# hamp1.net
KiCad netlist of a schematic drawn in EAGLE
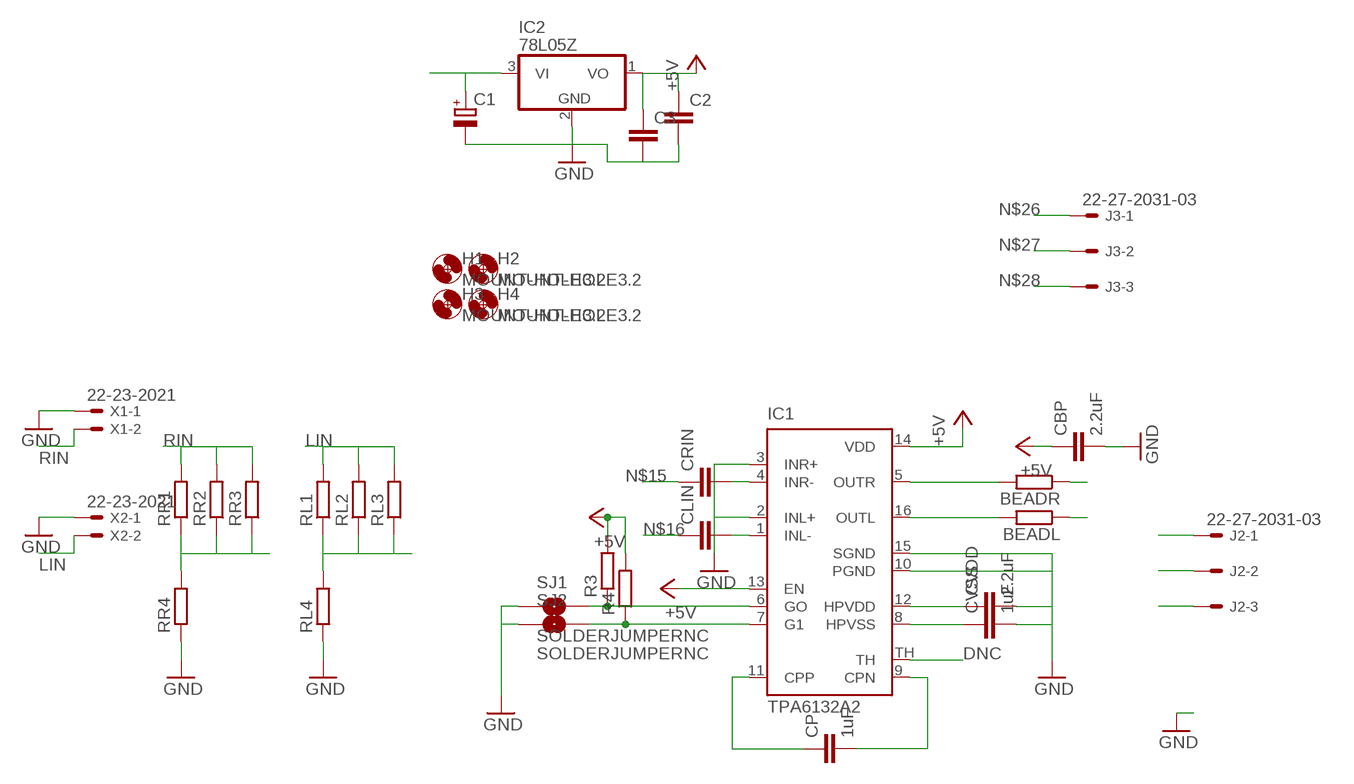
[diagram p0: schematic, sheet 1]

(export (version "E")
  (design (tool "Eeschema 10.0.6"))
  (components
    (comp (ref "BEADL")
      (value "R-EU_R0805")
      (footprint "eagle-import:R0805")
      (libsource (lib "eagle-import") (part "R-EU_R0805"))
    )
    (comp (ref "BEADR")
      (value "R-EU_R0805")
      (footprint "eagle-import:R0805")
      (libsource (lib "eagle-import") (part "R-EU_R0805"))
    )
    (comp (ref "C1")
      (value "CPOL-EUF")
      (footprint "eagle-import:PANASONIC_F")
      (libsource (lib "eagle-import") (part "CPOL-EUF"))
    )
    (comp (ref "C2")
      (value "C-EUC1210")
      (footprint "eagle-import:C1210")
      (libsource (lib "eagle-import") (part "resistor_C-EUC1210"))
    )
    (comp (ref "C3")
      (value "C-EUC0805")
      (footprint "eagle-import:C0805")
      (libsource (lib "eagle-import") (part "resistor_C-EUC0805"))
    )
    (comp (ref "CBP")
      (value "2.2uF")
      (footprint "eagle-import:C0805")
      (libsource (lib "eagle-import") (part "resistor_C-EUC0805"))
    )
    (comp (ref "CLIN")
      (value "C-EU050-055X075")
      (footprint "eagle-import:C050-055X075")
      (libsource (lib "eagle-import") (part "C-EU050-055X075"))
    )
    (comp (ref "CP")
      (value "1uF")
      (footprint "eagle-import:C0805")
      (libsource (lib "eagle-import") (part "resistor_C-EUC0805"))
    )
    (comp (ref "CRIN")
      (value "C-EU050-055X075")
      (footprint "eagle-import:C050-055X075")
      (libsource (lib "eagle-import") (part "C-EU050-055X075"))
    )
    (comp (ref "CVDD")
      (value "2.2uF")
      (footprint "eagle-import:C0805")
      (libsource (lib "eagle-import") (part "resistor_C-EUC0805"))
    )
    (comp (ref "CVSS")
      (value "1uF")
      (footprint "eagle-import:C0805")
      (libsource (lib "eagle-import") (part "resistor_C-EUC0805"))
    )
    (comp (ref "H1")
      (value "MOUNT-HOLE3.2")
      (footprint "eagle-import:3,2")
      (libsource (lib "eagle-import") (part "MOUNT-HOLE3.2"))
    )
    (comp (ref "H2")
      (value "MOUNT-HOLE3.2")
      (footprint "eagle-import:3,2")
      (libsource (lib "eagle-import") (part "MOUNT-HOLE3.2"))
    )
    (comp (ref "H3")
      (value "MOUNT-HOLE3.2")
      (footprint "eagle-import:3,2")
      (libsource (lib "eagle-import") (part "MOUNT-HOLE3.2"))
    )
    (comp (ref "H4")
      (value "MOUNT-HOLE3.2")
      (footprint "eagle-import:3,2")
      (libsource (lib "eagle-import") (part "MOUNT-HOLE3.2"))
    )
    (comp (ref "IC1")
      (value "TPA6132A2")
      (footprint "eagle-import:QFN16")
      (fields (field (name "MPN") "TPA6132A2RTET"))
      (libsource (lib "eagle-import") (part "TPA6132A2"))
    )
    (comp (ref "IC2")
      (value "78L05Z")
      (footprint "eagle-import:TO92")
      (libsource (lib "eagle-import") (part "78ZL05"))
    )
    (comp (ref "J2")
      (value "22-27-2031-03")
      (footprint "eagle-import:6410-03")
      (fields (field (name "OC_FARNELL") "unknown") (field (name "OC_NEWARK") "unknown"))
      (libsource (lib "eagle-import") (part "22-?-0327-2031"))
    )
    (comp (ref "J3")
      (value "22-27-2031-03")
      (footprint "eagle-import:6410-03")
      (fields (field (name "OC_FARNELL") "unknown") (field (name "OC_NEWARK") "unknown"))
      (libsource (lib "eagle-import") (part "22-?-0327-2031"))
    )
    (comp (ref "R3")
      (value "R-EU_R0805")
      (footprint "eagle-import:R0805")
      (libsource (lib "eagle-import") (part "R-EU_R0805"))
    )
    (comp (ref "R4")
      (value "R-EU_R0805")
      (footprint "eagle-import:R0805")
      (libsource (lib "eagle-import") (part "R-EU_R0805"))
    )
    (comp (ref "RL1")
      (value "R-EU_R0805")
      (footprint "eagle-import:R0805")
      (libsource (lib "eagle-import") (part "R-EU_R0805"))
    )
    (comp (ref "RL2")
      (value "R-EU_R0805")
      (footprint "eagle-import:R0805")
      (libsource (lib "eagle-import") (part "R-EU_R0805"))
    )
    (comp (ref "RL3")
      (value "R-EU_R0805")
      (footprint "eagle-import:R0805")
      (libsource (lib "eagle-import") (part "R-EU_R0805"))
    )
    (comp (ref "RL4")
      (value "R-EU_R0805")
      (footprint "eagle-import:R0805")
      (libsource (lib "eagle-import") (part "R-EU_R0805"))
    )
    (comp (ref "RR1")
      (value "R-EU_R0805")
      (footprint "eagle-import:R0805")
      (libsource (lib "eagle-import") (part "R-EU_R0805"))
    )
    (comp (ref "RR2")
      (value "R-EU_R0805")
      (footprint "eagle-import:R0805")
      (libsource (lib "eagle-import") (part "R-EU_R0805"))
    )
    (comp (ref "RR3")
      (value "R-EU_R0805")
      (footprint "eagle-import:R0805")
      (libsource (lib "eagle-import") (part "R-EU_R0805"))
    )
    (comp (ref "RR4")
      (value "R-EU_R0805")
      (footprint "eagle-import:R0805")
      (libsource (lib "eagle-import") (part "R-EU_R0805"))
    )
    (comp (ref "SJ1")
      (value "SOLDERJUMPERNC")
      (footprint "eagle-import:SJ_2S")
      (libsource (lib "eagle-import") (part "SOLDERJUMPERNC"))
    )
    (comp (ref "SJ2")
      (value "SOLDERJUMPERNC")
      (footprint "eagle-import:SJ_2S")
      (libsource (lib "eagle-import") (part "SOLDERJUMPERNC"))
    )
    (comp (ref "X1")
      (value "22-23-2021")
      (footprint "eagle-import:22-23-2021")
      (fields (field (name "MF") "MOLEX"))
      (libsource (lib "eagle-import") (part "22-23-2021"))
    )
    (comp (ref "X2")
      (value "22-23-2021")
      (footprint "eagle-import:22-23-2021")
      (fields (field (name "MF") "MOLEX"))
      (libsource (lib "eagle-import") (part "22-23-2021"))
    )
  )
  (nets
    (net (code "1") (name "+5V") (class "Default")
      (node (ref "C2") (pin "1") (pinfunction "1_1") (pintype "passive"))
      (node (ref "C3") (pin "1") (pinfunction "1_1") (pintype "passive"))
      (node (ref "CBP") (pin "1") (pinfunction "1_1") (pintype "passive"))
      (node (ref "IC1") (pin "13") (pinfunction "EN_13") (pintype "input"))
      (node (ref "IC1") (pin "14") (pinfunction "VDD_14") (pintype "power_in"))
      (node (ref "IC2") (pin "1") (pinfunction "VO_1") (pintype "passive"))
      (node (ref "R3") (pin "2") (pinfunction "2_2") (pintype "passive"))
      (node (ref "R4") (pin "2") (pinfunction "2_2") (pintype "passive"))
    )
    (net (code "2") (name "/DNC") (class "Default")
      (node (ref "IC1") (pin "TH") (pinfunction "TH_TH") (pintype "passive"))
    )
    (net (code "3") (name "/LIN") (class "Default")
      (node (ref "RL1") (pin "2") (pinfunction "2_2") (pintype "passive"))
      (node (ref "RL2") (pin "2") (pinfunction "2_2") (pintype "passive"))
      (node (ref "RL3") (pin "2") (pinfunction "2_2") (pintype "passive"))
      (node (ref "X2") (pin "2") (pinfunction "S_2") (pintype "passive"))
    )
    (net (code "4") (name "/N$6") (class "Default")
      (node (ref "BEADR") (pin "1") (pinfunction "1_1") (pintype "passive"))
      (node (ref "J2") (pin "2") (pinfunction "S_2") (pintype "passive"))
    )
    (net (code "5") (name "/N$14") (class "Default")
      (node (ref "BEADL") (pin "1") (pinfunction "1_1") (pintype "passive"))
      (node (ref "J2") (pin "3") (pinfunction "S_3") (pintype "passive"))
    )
    (net (code "6") (name "/N$15") (class "Default")
      (node (ref "CRIN") (pin "1") (pinfunction "1_1") (pintype "passive"))
      (node (ref "RR1") (pin "1") (pinfunction "1_1") (pintype "passive"))
      (node (ref "RR2") (pin "1") (pinfunction "1_1") (pintype "passive"))
      (node (ref "RR3") (pin "1") (pinfunction "1_1") (pintype "passive"))
      (node (ref "RR4") (pin "2") (pinfunction "2_2") (pintype "passive"))
    )
    (net (code "7") (name "/N$16") (class "Default")
      (node (ref "CLIN") (pin "1") (pinfunction "1_1") (pintype "passive"))
      (node (ref "RL1") (pin "1") (pinfunction "1_1") (pintype "passive"))
      (node (ref "RL2") (pin "1") (pinfunction "1_1") (pintype "passive"))
      (node (ref "RL3") (pin "1") (pinfunction "1_1") (pintype "passive"))
      (node (ref "RL4") (pin "2") (pinfunction "2_2") (pintype "passive"))
    )
    (net (code "8") (name "/N$26") (class "Default")
      (node (ref "J3") (pin "1") (pinfunction "S_1") (pintype "passive"))
    )
    (net (code "9") (name "/N$27") (class "Default")
      (node (ref "J3") (pin "2") (pinfunction "S_2") (pintype "passive"))
    )
    (net (code "10") (name "/N$28") (class "Default")
      (node (ref "J3") (pin "3") (pinfunction "S_3") (pintype "passive"))
    )
    (net (code "11") (name "/RIN") (class "Default")
      (node (ref "RR1") (pin "2") (pinfunction "2_2") (pintype "passive"))
      (node (ref "RR2") (pin "2") (pinfunction "2_2") (pintype "passive"))
      (node (ref "RR3") (pin "2") (pinfunction "2_2") (pintype "passive"))
      (node (ref "X1") (pin "2") (pinfunction "S_2") (pintype "passive"))
    )
    (net (code "12") (name "GND") (class "Default")
      (node (ref "C1") (pin "-") (pinfunction "-_-") (pintype "passive"))
      (node (ref "C2") (pin "2") (pinfunction "2_2") (pintype "passive"))
      (node (ref "C3") (pin "2") (pinfunction "2_2") (pintype "passive"))
      (node (ref "CBP") (pin "2") (pinfunction "2_2") (pintype "passive"))
      (node (ref "CVDD") (pin "2") (pinfunction "2_2") (pintype "passive"))
      (node (ref "CVSS") (pin "2") (pinfunction "2_2") (pintype "passive"))
      (node (ref "IC1") (pin "10") (pinfunction "PGND_10") (pintype "power_in"))
      (node (ref "IC1") (pin "15") (pinfunction "SGND_15") (pintype "power_in"))
      (node (ref "IC1") (pin "2") (pinfunction "INL+_2") (pintype "input"))
      (node (ref "IC1") (pin "3") (pinfunction "INR+_3") (pintype "input"))
      (node (ref "IC2") (pin "2") (pinfunction "GND_2") (pintype "passive"))
      (node (ref "J2") (pin "1") (pinfunction "S_1") (pintype "passive"))
      (node (ref "RL4") (pin "1") (pinfunction "1_1") (pintype "passive"))
      (node (ref "RR4") (pin "1") (pinfunction "1_1") (pintype "passive"))
      (node (ref "SJ1") (pin "1") (pinfunction "1_1") (pintype "passive"))
      (node (ref "SJ2") (pin "1") (pinfunction "1_1") (pintype "passive"))
      (node (ref "X1") (pin "1") (pinfunction "S_1") (pintype "passive"))
      (node (ref "X2") (pin "1") (pinfunction "S_1") (pintype "passive"))
    )
    (net (code "13") (name "Net-(IC1-CPN)") (class "Default")
      (node (ref "CP") (pin "2") (pinfunction "2_2") (pintype "passive"))
      (node (ref "IC1") (pin "9") (pinfunction "CPN_9") (pintype "passive"))
    )
    (net (code "14") (name "Net-(IC1-CPP)") (class "Default")
      (node (ref "CP") (pin "1") (pinfunction "1_1") (pintype "passive"))
      (node (ref "IC1") (pin "11") (pinfunction "CPP_11") (pintype "passive"))
    )
    (net (code "15") (name "Net-(IC1-G1)") (class "Default")
      (node (ref "IC1") (pin "7") (pinfunction "G1_7") (pintype "input"))
      (node (ref "R4") (pin "1") (pinfunction "1_1") (pintype "passive"))
      (node (ref "SJ2") (pin "2") (pinfunction "2_2") (pintype "passive"))
    )
    (net (code "16") (name "Net-(IC1-GO)") (class "Default")
      (node (ref "IC1") (pin "6") (pinfunction "GO_6") (pintype "input"))
      (node (ref "R3") (pin "1") (pinfunction "1_1") (pintype "passive"))
      (node (ref "SJ1") (pin "2") (pinfunction "2_2") (pintype "passive"))
    )
    (net (code "17") (name "Net-(IC1-HPVDD)") (class "Default")
      (node (ref "CVDD") (pin "1") (pinfunction "1_1") (pintype "passive"))
      (node (ref "IC1") (pin "12") (pinfunction "HPVDD_12") (pintype "passive"))
    )
    (net (code "18") (name "Net-(IC1-HPVSS)") (class "Default")
      (node (ref "CVSS") (pin "1") (pinfunction "1_1") (pintype "passive"))
      (node (ref "IC1") (pin "8") (pinfunction "HPVSS_8") (pintype "passive"))
    )
    (net (code "19") (name "Net-(IC1-INL-)") (class "Default")
      (node (ref "CLIN") (pin "2") (pinfunction "2_2") (pintype "passive"))
      (node (ref "IC1") (pin "1") (pinfunction "INL-_1") (pintype "input"))
    )
    (net (code "20") (name "Net-(IC1-INR-)") (class "Default")
      (node (ref "CRIN") (pin "2") (pinfunction "2_2") (pintype "passive"))
      (node (ref "IC1") (pin "4") (pinfunction "INR-_4") (pintype "input"))
    )
    (net (code "21") (name "Net-(IC1-OUTL)") (class "Default")
      (node (ref "BEADL") (pin "2") (pinfunction "2_2") (pintype "passive"))
      (node (ref "IC1") (pin "16") (pinfunction "OUTL_16") (pintype "output"))
    )
    (net (code "22") (name "Net-(IC1-OUTR)") (class "Default")
      (node (ref "BEADR") (pin "2") (pinfunction "2_2") (pintype "passive"))
      (node (ref "IC1") (pin "5") (pinfunction "OUTR_5") (pintype "output"))
    )
    (net (code "23") (name "Net-(IC2-VI)") (class "Default")
      (node (ref "C1") (pin "+") (pinfunction "+_+") (pintype "passive"))
      (node (ref "IC2") (pin "3") (pinfunction "VI_3") (pintype "input"))
    )
  )
)
